# eeZeeLED.net
KiCad netlist of a schematic drawn in EAGLE
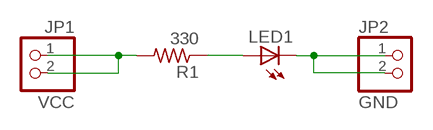
[diagram p0: schematic, sheet 1]

(export (version "E")
  (design (tool "Eeschema 10.0.6"))
  (components
    (comp (ref "JP1")
      (value "VCC")
      (footprint "eagle-import:1X02-S")
      (libsource (lib "eagle-import") (part "PINHD-1X02_2.54-S"))
    )
    (comp (ref "JP2")
      (value "GND")
      (footprint "eagle-import:1X02-S")
      (libsource (lib "eagle-import") (part "PINHD-1X02_2.54-S"))
    )
    (comp (ref "LED1")
      (value "LEDCHIPLED_0805")
      (footprint "eagle-import:CHIPLED_0805")
      (libsource (lib "eagle-import") (part "LEDCHIPLED_0805"))
    )
    (comp (ref "R1")
      (value "330")
      (footprint "eagle-import:R0603")
      (libsource (lib "eagle-import") (part "R-US_R0603"))
    )
  )
  (nets
    (net (code "1") (name "Net-(JP1-Pad1)") (class "Default")
      (node (ref "JP1") (pin "1") (pinfunction "1_1") (pintype "passive"))
      (node (ref "JP1") (pin "2") (pinfunction "2_2") (pintype "passive"))
      (node (ref "R1") (pin "2") (pinfunction "2_2") (pintype "passive"))
    )
    (net (code "2") (name "Net-(JP2-Pad1)") (class "Default")
      (node (ref "JP2") (pin "1") (pinfunction "1_1") (pintype "passive"))
      (node (ref "JP2") (pin "2") (pinfunction "2_2") (pintype "passive"))
      (node (ref "LED1") (pin "C") (pinfunction "C_C") (pintype "passive"))
    )
    (net (code "3") (name "Net-(LED1-PadA)") (class "Default")
      (node (ref "LED1") (pin "A") (pinfunction "A_A") (pintype "passive"))
      (node (ref "R1") (pin "1") (pinfunction "1_1") (pintype "passive"))
    )
  )
)
